# Driver-Sheet.net
KiCad netlist of a schematic drawn in Altium Designer
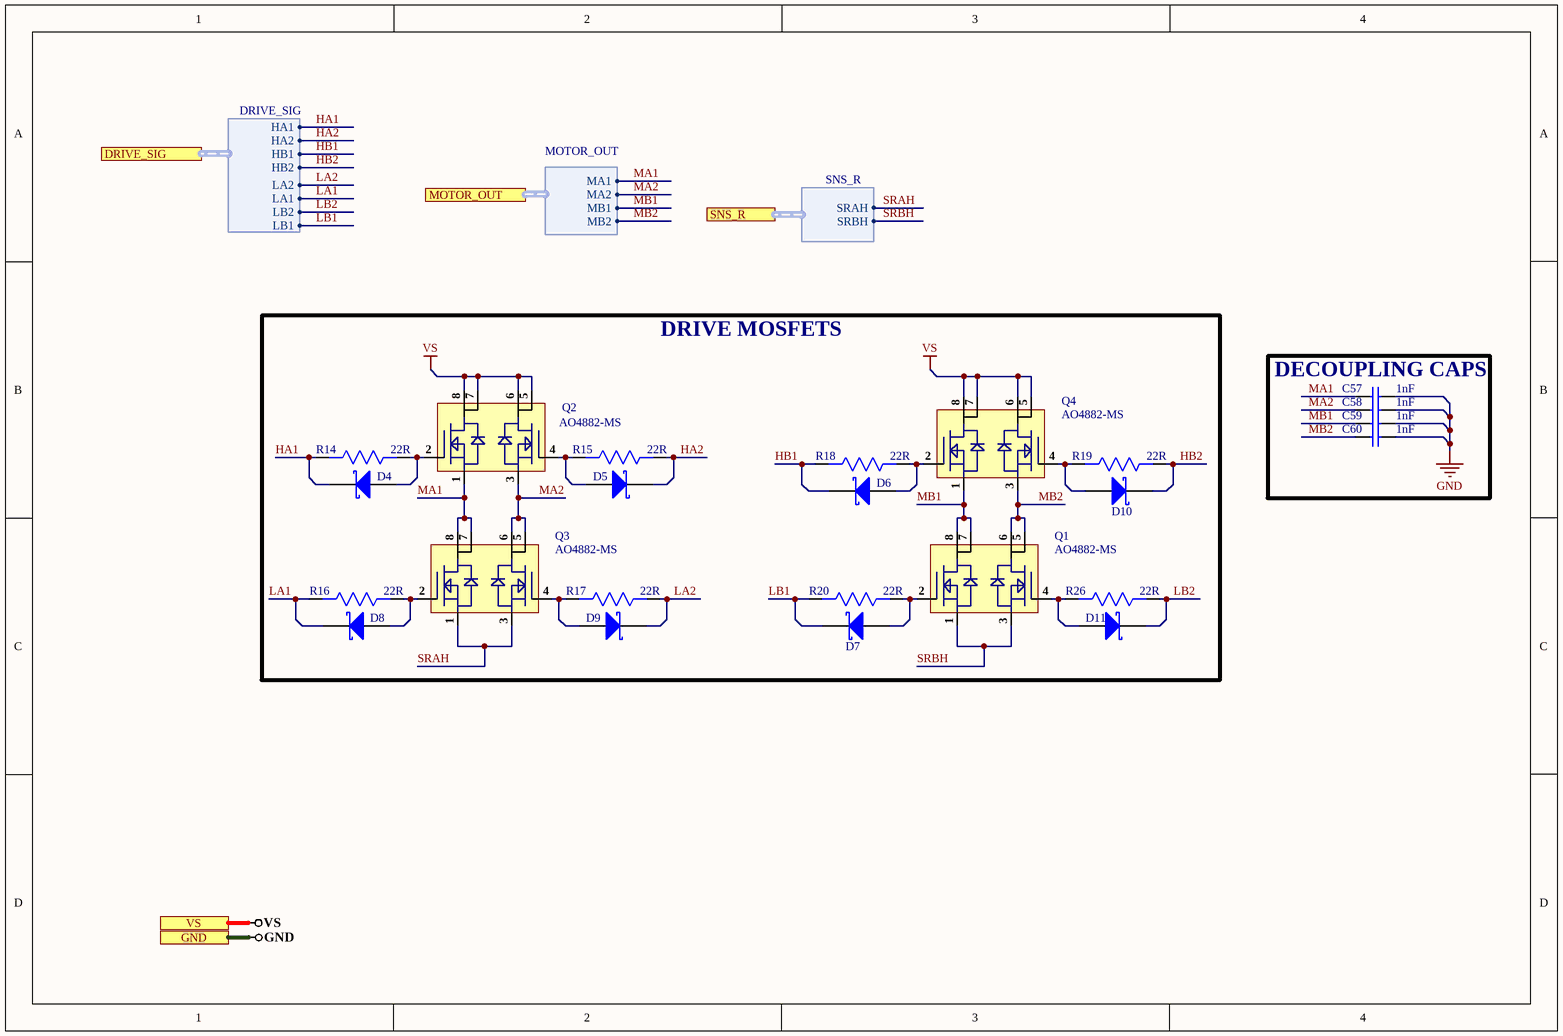
[diagram p0: Driver-Sheet.SchDoc]

(export (version "E")
  (design (tool "Eeschema 10.0.6"))
  (components
    (comp (ref "C57")
      (value "1nF")
      (footprint "Cap 0603")
      (description "CAP CER 1nF 100V X7R 0603")
      (fields
        (field (name "MANUFACTURER") "Samsung")
        (field (name "MANUFACTURER PART NUMBER") "CL10B102KC8NNNC")
      )
      (libsource (lib "Cole_Benson") (part "CL10B102KC8NNNC"))
    )
    (comp (ref "C58")
      (value "1nF")
      (footprint "Cap 0603")
      (description "CAP CER 1nF 100V X7R 0603")
      (fields
        (field (name "MANUFACTURER") "Samsung")
        (field (name "MANUFACTURER PART NUMBER") "CL10B102KC8NNNC")
      )
      (libsource (lib "Cole_Benson") (part "CL10B102KC8NNNC"))
    )
    (comp (ref "C59")
      (value "1nF")
      (footprint "Cap 0603")
      (description "CAP CER 1nF 100V X7R 0603")
      (fields
        (field (name "MANUFACTURER") "Samsung")
        (field (name "MANUFACTURER PART NUMBER") "CL10B102KC8NNNC")
      )
      (libsource (lib "Cole_Benson") (part "CL10B102KC8NNNC"))
    )
    (comp (ref "C60")
      (value "1nF")
      (footprint "Cap 0603")
      (description "CAP CER 1nF 100V X7R 0603")
      (fields
        (field (name "MANUFACTURER") "Samsung")
        (field (name "MANUFACTURER PART NUMBER") "CL10B102KC8NNNC")
      )
      (libsource (lib "Cole_Benson") (part "CL10B102KC8NNNC"))
    )
    (comp (ref "D4")
      (value "CRS01(TE85L,Q,M)")
      (footprint "CRS01(TE85L,Q,M)")
      (description "DIODE SCHOTTKY 30V 1A SOD123F")
      (fields (field (name "MANUFACTURER") "TOSHIBA"))
      (libsource (lib "Cole_Benson") (part "CRS01(TE85L,Q,M)"))
    )
    (comp (ref "D5")
      (value "CRS01(TE85L,Q,M)")
      (footprint "CRS01(TE85L,Q,M)")
      (description "DIODE SCHOTTKY 30V 1A SOD123F")
      (fields (field (name "MANUFACTURER") "TOSHIBA"))
      (libsource (lib "Cole_Benson") (part "CRS01(TE85L,Q,M)"))
    )
    (comp (ref "D6")
      (value "CRS01(TE85L,Q,M)")
      (footprint "CRS01(TE85L,Q,M)")
      (description "DIODE SCHOTTKY 30V 1A SOD123F")
      (fields (field (name "MANUFACTURER") "TOSHIBA"))
      (libsource (lib "Cole_Benson") (part "CRS01(TE85L,Q,M)"))
    )
    (comp (ref "D7")
      (value "CRS01(TE85L,Q,M)")
      (footprint "CRS01(TE85L,Q,M)")
      (description "DIODE SCHOTTKY 30V 1A SOD123F")
      (fields (field (name "MANUFACTURER") "TOSHIBA"))
      (libsource (lib "Cole_Benson") (part "CRS01(TE85L,Q,M)"))
    )
    (comp (ref "D8")
      (value "CRS01(TE85L,Q,M)")
      (footprint "CRS01(TE85L,Q,M)")
      (description "DIODE SCHOTTKY 30V 1A SOD123F")
      (fields (field (name "MANUFACTURER") "TOSHIBA"))
      (libsource (lib "Cole_Benson") (part "CRS01(TE85L,Q,M)"))
    )
    (comp (ref "D9")
      (value "CRS01(TE85L,Q,M)")
      (footprint "CRS01(TE85L,Q,M)")
      (description "DIODE SCHOTTKY 30V 1A SOD123F")
      (fields (field (name "MANUFACTURER") "TOSHIBA"))
      (libsource (lib "Cole_Benson") (part "CRS01(TE85L,Q,M)"))
    )
    (comp (ref "D10")
      (value "CRS01(TE85L,Q,M)")
      (footprint "CRS01(TE85L,Q,M)")
      (description "DIODE SCHOTTKY 30V 1A SOD123F")
      (fields (field (name "MANUFACTURER") "TOSHIBA"))
      (libsource (lib "Cole_Benson") (part "CRS01(TE85L,Q,M)"))
    )
    (comp (ref "D11")
      (value "CRS01(TE85L,Q,M)")
      (footprint "CRS01(TE85L,Q,M)")
      (description "DIODE SCHOTTKY 30V 1A SOD123F")
      (fields (field (name "MANUFACTURER") "TOSHIBA"))
      (libsource (lib "Cole_Benson") (part "CRS01(TE85L,Q,M)"))
    )
    (comp (ref "Q1")
      (value "AO4882-MS")
      (footprint "AO4882-MS")
      (fields (field (name "MANUFACTURER") "MSKSEMI"))
      (libsource (lib "Cole_Benson") (part "AO4882-MS"))
    )
    (comp (ref "Q2")
      (value "AO4882-MS")
      (footprint "AO4882-MS")
      (fields (field (name "MANUFACTURER") "MSKSEMI"))
      (libsource (lib "Cole_Benson") (part "AO4882-MS"))
    )
    (comp (ref "Q3")
      (value "AO4882-MS")
      (footprint "AO4882-MS")
      (fields (field (name "MANUFACTURER") "MSKSEMI"))
      (libsource (lib "Cole_Benson") (part "AO4882-MS"))
    )
    (comp (ref "Q4")
      (value "AO4882-MS")
      (footprint "AO4882-MS")
      (fields (field (name "MANUFACTURER") "MSKSEMI"))
      (libsource (lib "Cole_Benson") (part "AO4882-MS"))
    )
    (comp (ref "R14")
      (value "22R")
      (footprint "Res0603")
      (description "22Ω 0603 Chip Resistor - Surface Mount ROHS")
      (fields
        (field (name "MANUFACTURER") "UNI-ROYAL")
        (field (name "MANUFACTURER PART NUMBER") "0603WAF220JT5E")
      )
      (libsource (lib "Cole_Benson") (part "0603WAF220JT5E"))
    )
    (comp (ref "R15")
      (value "22R")
      (footprint "Res0603")
      (description "22Ω 0603 Chip Resistor - Surface Mount ROHS")
      (fields
        (field (name "MANUFACTURER") "UNI-ROYAL")
        (field (name "MANUFACTURER PART NUMBER") "0603WAF220JT5E")
      )
      (libsource (lib "Cole_Benson") (part "0603WAF220JT5E"))
    )
    (comp (ref "R16")
      (value "22R")
      (footprint "Res0603")
      (description "22Ω 0603 Chip Resistor - Surface Mount ROHS")
      (fields
        (field (name "MANUFACTURER") "UNI-ROYAL")
        (field (name "MANUFACTURER PART NUMBER") "0603WAF220JT5E")
      )
      (libsource (lib "Cole_Benson") (part "0603WAF220JT5E"))
    )
    (comp (ref "R17")
      (value "22R")
      (footprint "Res0603")
      (description "22Ω 0603 Chip Resistor - Surface Mount ROHS")
      (fields
        (field (name "MANUFACTURER") "UNI-ROYAL")
        (field (name "MANUFACTURER PART NUMBER") "0603WAF220JT5E")
      )
      (libsource (lib "Cole_Benson") (part "0603WAF220JT5E"))
    )
    (comp (ref "R18")
      (value "22R")
      (footprint "Res0603")
      (description "22Ω 0603 Chip Resistor - Surface Mount ROHS")
      (fields
        (field (name "MANUFACTURER") "UNI-ROYAL")
        (field (name "MANUFACTURER PART NUMBER") "0603WAF220JT5E")
      )
      (libsource (lib "Cole_Benson") (part "0603WAF220JT5E"))
    )
    (comp (ref "R19")
      (value "22R")
      (footprint "Res0603")
      (description "22Ω 0603 Chip Resistor - Surface Mount ROHS")
      (fields
        (field (name "MANUFACTURER") "UNI-ROYAL")
        (field (name "MANUFACTURER PART NUMBER") "0603WAF220JT5E")
      )
      (libsource (lib "Cole_Benson") (part "0603WAF220JT5E"))
    )
    (comp (ref "R20")
      (value "22R")
      (footprint "Res0603")
      (description "22Ω 0603 Chip Resistor - Surface Mount ROHS")
      (fields
        (field (name "MANUFACTURER") "UNI-ROYAL")
        (field (name "MANUFACTURER PART NUMBER") "0603WAF220JT5E")
      )
      (libsource (lib "Cole_Benson") (part "0603WAF220JT5E"))
    )
    (comp (ref "R26")
      (value "22R")
      (footprint "Res0603")
      (description "22Ω 0603 Chip Resistor - Surface Mount ROHS")
      (fields
        (field (name "MANUFACTURER") "UNI-ROYAL")
        (field (name "MANUFACTURER PART NUMBER") "0603WAF220JT5E")
      )
      (libsource (lib "Cole_Benson") (part "0603WAF220JT5E"))
    )
  )
  (nets
    (net (code "4") (name "/HA1") (class "Default")
      (node (ref "D4") (pin "2") (pinfunction "K_2") (pintype "passive"))
      (node (ref "R14") (pin "2") (pintype "passive"))
    )
    (net (code "5") (name "/HA2") (class "Default")
      (node (ref "D5") (pin "2") (pinfunction "K_2") (pintype "passive"))
      (node (ref "R15") (pin "1") (pintype "passive"))
    )
    (net (code "6") (name "/HB1") (class "Default")
      (node (ref "D6") (pin "2") (pinfunction "K_2") (pintype "passive"))
      (node (ref "R18") (pin "2") (pintype "passive"))
    )
    (net (code "7") (name "/HB2") (class "Default")
      (node (ref "D10") (pin "2") (pinfunction "K_2") (pintype "passive"))
      (node (ref "R19") (pin "1") (pintype "passive"))
    )
    (net (code "8") (name "/LA1") (class "Default")
      (node (ref "D8") (pin "2") (pinfunction "K_2") (pintype "passive"))
      (node (ref "R16") (pin "2") (pintype "passive"))
    )
    (net (code "9") (name "/LA2") (class "Default")
      (node (ref "D9") (pin "2") (pinfunction "K_2") (pintype "passive"))
      (node (ref "R17") (pin "1") (pintype "passive"))
    )
    (net (code "10") (name "/LB1") (class "Default")
      (node (ref "D7") (pin "2") (pinfunction "K_2") (pintype "passive"))
      (node (ref "R20") (pin "2") (pintype "passive"))
    )
    (net (code "11") (name "/LB2") (class "Default")
      (node (ref "D11") (pin "2") (pinfunction "K_2") (pintype "passive"))
      (node (ref "R26") (pin "1") (pintype "passive"))
    )
    (net (code "12") (name "/MA1") (class "Default")
      (node (ref "C57") (pin "1") (pinfunction "1_1") (pintype "passive"))
      (node (ref "Q2") (pin "1") (pinfunction "S1_1") (pintype "passive"))
      (node (ref "Q3") (pin "7") (pinfunction "D1_7") (pintype "passive"))
      (node (ref "Q3") (pin "8") (pinfunction "D1_8") (pintype "passive"))
    )
    (net (code "13") (name "/MA2") (class "Default")
      (node (ref "C58") (pin "1") (pinfunction "1_1") (pintype "passive"))
      (node (ref "Q2") (pin "3") (pinfunction "S2_3") (pintype "passive"))
      (node (ref "Q3") (pin "5") (pinfunction "D2_5") (pintype "passive"))
      (node (ref "Q3") (pin "6") (pinfunction "D2_6") (pintype "passive"))
    )
    (net (code "14") (name "/MB1") (class "Default")
      (node (ref "C59") (pin "1") (pinfunction "1_1") (pintype "passive"))
      (node (ref "Q1") (pin "7") (pinfunction "D1_7") (pintype "passive"))
      (node (ref "Q1") (pin "8") (pinfunction "D1_8") (pintype "passive"))
      (node (ref "Q4") (pin "1") (pinfunction "S1_1") (pintype "passive"))
    )
    (net (code "15") (name "/MB2") (class "Default")
      (node (ref "C60") (pin "1") (pinfunction "1_1") (pintype "passive"))
      (node (ref "Q1") (pin "5") (pinfunction "D2_5") (pintype "passive"))
      (node (ref "Q1") (pin "6") (pinfunction "D2_6") (pintype "passive"))
      (node (ref "Q4") (pin "3") (pinfunction "S2_3") (pintype "passive"))
    )
    (net (code "16") (name "/SRAH") (class "Default")
      (node (ref "Q3") (pin "1") (pinfunction "S1_1") (pintype "passive"))
      (node (ref "Q3") (pin "3") (pinfunction "S2_3") (pintype "passive"))
    )
    (net (code "17") (name "/SRBH") (class "Default")
      (node (ref "Q1") (pin "1") (pinfunction "S1_1") (pintype "passive"))
      (node (ref "Q1") (pin "3") (pinfunction "S2_3") (pintype "passive"))
    )
    (net (code "21") (name "GND") (class "Default")
      (node (ref "C57") (pin "2") (pinfunction "2_2") (pintype "passive"))
      (node (ref "C58") (pin "2") (pinfunction "2_2") (pintype "passive"))
      (node (ref "C59") (pin "2") (pinfunction "2_2") (pintype "passive"))
      (node (ref "C60") (pin "2") (pinfunction "2_2") (pintype "passive"))
    )
    (net (code "22") (name "Net-(D4-A)") (class "Default")
      (node (ref "D4") (pin "1") (pinfunction "A_1") (pintype "passive"))
      (node (ref "Q2") (pin "2") (pinfunction "G1_2") (pintype "passive"))
      (node (ref "R14") (pin "1") (pintype "passive"))
    )
    (net (code "23") (name "Net-(D5-A)") (class "Default")
      (node (ref "D5") (pin "1") (pinfunction "A_1") (pintype "passive"))
      (node (ref "Q2") (pin "4") (pinfunction "G2_4") (pintype "passive"))
      (node (ref "R15") (pin "2") (pintype "passive"))
    )
    (net (code "24") (name "Net-(D6-A)") (class "Default")
      (node (ref "D6") (pin "1") (pinfunction "A_1") (pintype "passive"))
      (node (ref "Q4") (pin "2") (pinfunction "G1_2") (pintype "passive"))
      (node (ref "R18") (pin "1") (pintype "passive"))
    )
    (net (code "25") (name "Net-(D7-A)") (class "Default")
      (node (ref "D7") (pin "1") (pinfunction "A_1") (pintype "passive"))
      (node (ref "Q1") (pin "2") (pinfunction "G1_2") (pintype "passive"))
      (node (ref "R20") (pin "1") (pintype "passive"))
    )
    (net (code "26") (name "Net-(D8-A)") (class "Default")
      (node (ref "D8") (pin "1") (pinfunction "A_1") (pintype "passive"))
      (node (ref "Q3") (pin "2") (pinfunction "G1_2") (pintype "passive"))
      (node (ref "R16") (pin "1") (pintype "passive"))
    )
    (net (code "27") (name "Net-(D9-A)") (class "Default")
      (node (ref "D9") (pin "1") (pinfunction "A_1") (pintype "passive"))
      (node (ref "Q3") (pin "4") (pinfunction "G2_4") (pintype "passive"))
      (node (ref "R17") (pin "2") (pintype "passive"))
    )
    (net (code "28") (name "Net-(D10-A)") (class "Default")
      (node (ref "D10") (pin "1") (pinfunction "A_1") (pintype "passive"))
      (node (ref "Q4") (pin "4") (pinfunction "G2_4") (pintype "passive"))
      (node (ref "R19") (pin "2") (pintype "passive"))
    )
    (net (code "29") (name "Net-(D11-A)") (class "Default")
      (node (ref "D11") (pin "1") (pinfunction "A_1") (pintype "passive"))
      (node (ref "Q1") (pin "4") (pinfunction "G2_4") (pintype "passive"))
      (node (ref "R26") (pin "2") (pintype "passive"))
    )
    (net (code "30") (name "VS") (class "Default")
      (node (ref "Q2") (pin "5") (pinfunction "D2_5") (pintype "passive"))
      (node (ref "Q2") (pin "6") (pinfunction "D2_6") (pintype "passive"))
      (node (ref "Q2") (pin "7") (pinfunction "D1_7") (pintype "passive"))
      (node (ref "Q2") (pin "8") (pinfunction "D1_8") (pintype "passive"))
      (node (ref "Q4") (pin "5") (pinfunction "D2_5") (pintype "passive"))
      (node (ref "Q4") (pin "6") (pinfunction "D2_6") (pintype "passive"))
      (node (ref "Q4") (pin "7") (pinfunction "D1_7") (pintype "passive"))
      (node (ref "Q4") (pin "8") (pinfunction "D1_8") (pintype "passive"))
    )
  )
)
